# BLE112_Breakout_Board_v2_2.net
KiCad netlist of a schematic drawn in EAGLE
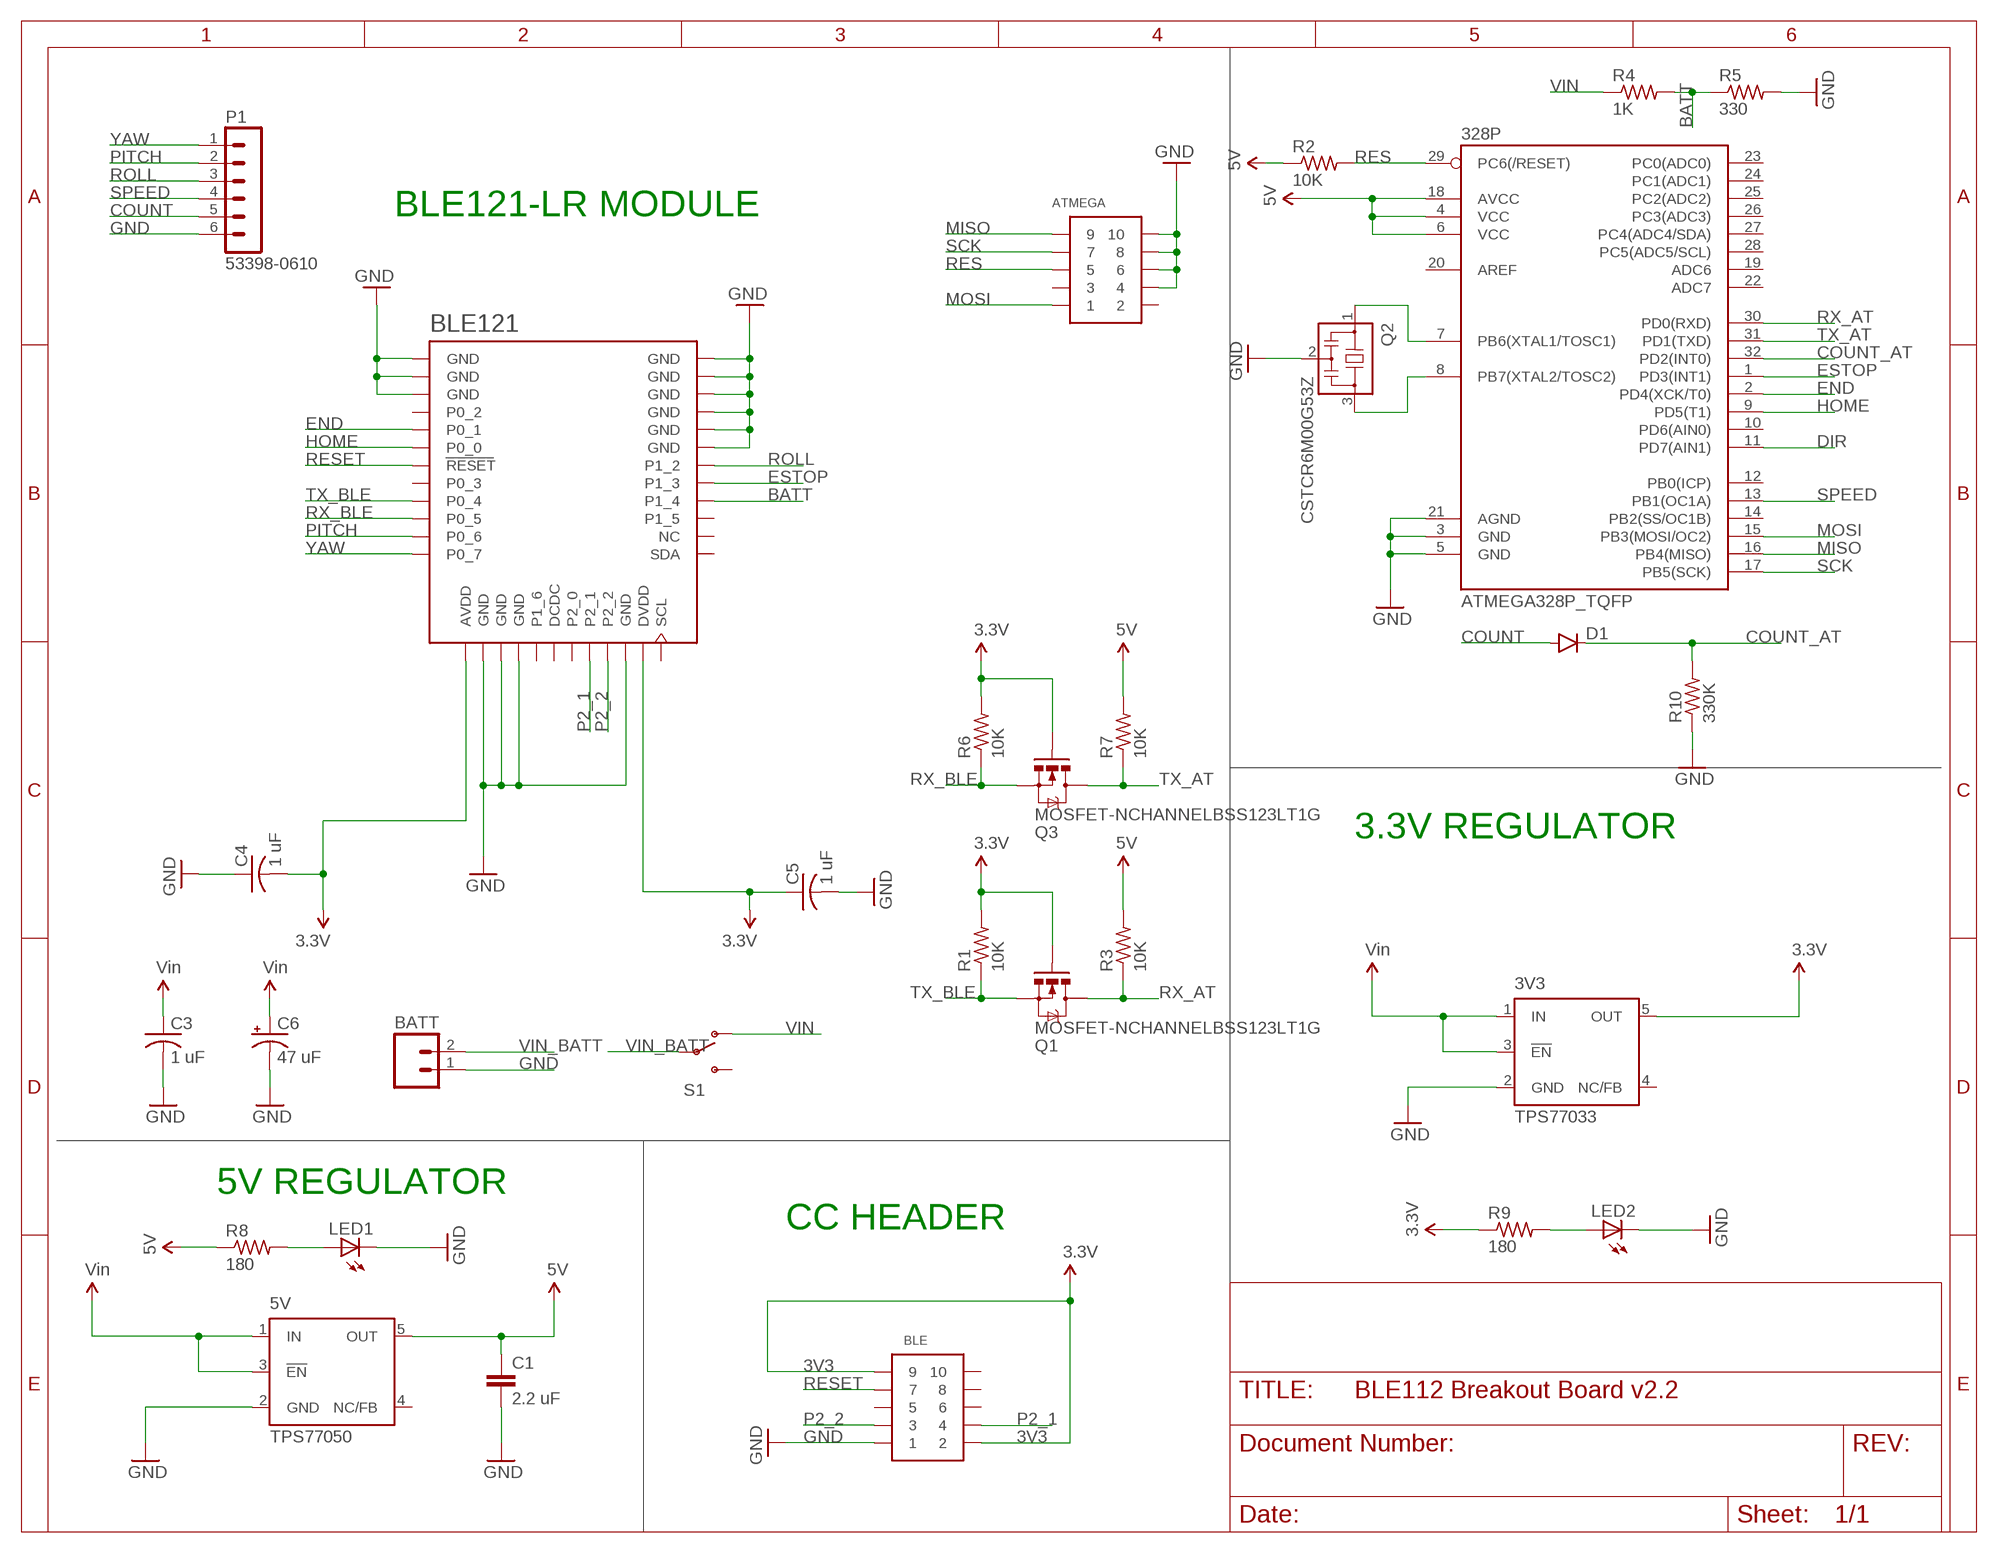
[diagram p0: schematic, sheet 1]

(export (version "E")
  (design (tool "Eeschema 10.0.6"))
  (components
    (comp (ref "3V3")
      (value "TPS77033")
      (footprint "eagle-import:SOT23-DBV")
      (fields (field (name "MF") "TEXAS INSTRUMENTS") (field (name "MPN") "TPS77033DBVT"))
      (libsource (lib "eagle-import") (part "TPS77033"))
    )
    (comp (ref "5V")
      (value "TPS77050")
      (footprint "eagle-import:SOT23-DBV")
      (fields (field (name "MF") "TEXAS INSTRUMENT CONNECTORS") (field (name "MPN") "TPS77050DBVT"))
      (libsource (lib "eagle-import") (part "TPS77050"))
    )
    (comp (ref "328P")
      (value "ATMEGA328P_TQFP")
      (footprint "eagle-import:TQFP32-08")
      (libsource (lib "eagle-import") (part "ATMEGA328P_TQFP"))
    )
    (comp (ref "ATMEGA")
      (value "CONN_5-2-FTSH-V")
      (footprint "eagle-import:FTSH-105-DV")
      (libsource (lib "eagle-import") (part "CONN_5-2-FTSH-V"))
    )
    (comp (ref "BATT")
      (value "M02JST-PTH-2")
      (footprint "eagle-import:JST-2-PTH")
      (libsource (lib "eagle-import") (part "M02JST-PTH-2"))
    )
    (comp (ref "BLE")
      (value "CONN_5-2-FTSH-V")
      (footprint "eagle-import:FTSH-105-DV")
      (libsource (lib "eagle-import") (part "CONN_5-2-FTSH-V"))
    )
    (comp (ref "BLE121")
      (value "BLE121LR-VISUAL-A")
      (footprint "eagle-import:BLE121LR-A")
      (libsource (lib "eagle-import") (part "BLE121LR-VISUAL-A"))
    )
    (comp (ref "C1")
      (value "2.2 uF")
      (footprint "eagle-import:0603-CAP")
      (libsource (lib "eagle-import") (part "CAP0603-CAP"))
    )
    (comp (ref "C3")
      (value "1 uF")
      (footprint "eagle-import:C0402")
      (libsource (lib "eagle-import") (part "C-USC0402"))
    )
    (comp (ref "C4")
      (value "1 uF")
      (footprint "eagle-import:C0402")
      (libsource (lib "eagle-import") (part "C-USC0402"))
    )
    (comp (ref "C5")
      (value "1 uF")
      (footprint "eagle-import:C0402")
      (libsource (lib "eagle-import") (part "C-USC0402"))
    )
    (comp (ref "C6")
      (value "47 uF")
      (footprint "eagle-import:PANASONIC_D")
      (libsource (lib "eagle-import") (part "CPOL-USD"))
    )
    (comp (ref "D1")
      (value "DIODESOT23")
      (footprint "eagle-import:SOT23-3")
      (libsource (lib "eagle-import") (part "DIODESOT23"))
    )
    (comp (ref "LED1")
      (value "LEDSML0603")
      (footprint "eagle-import:SML0603")
      (libsource (lib "eagle-import") (part "LEDSML0603"))
    )
    (comp (ref "LED2")
      (value "LEDSML0603")
      (footprint "eagle-import:SML0603")
      (libsource (lib "eagle-import") (part "LEDSML0603"))
    )
    (comp (ref "P1")
      (value "53398-0610")
      (footprint "eagle-import:53398-0610")
      (libsource (lib "eagle-import") (part "53398-0610"))
    )
    (comp (ref "Q1")
      (value "MOSFET-NCHANNELBSS123LT1G")
      (footprint "eagle-import:SOT23-3")
      (libsource (lib "eagle-import") (part "MOSFET-NCHANNELBSS123LT1G"))
    )
    (comp (ref "Q2")
      (value "CSTCR6M00G53Z")
      (footprint "eagle-import:CSTCR6M")
      (fields (field (name "MPN") "CSTCR6M00G53-R0"))
      (libsource (lib "eagle-import") (part "CSTCR6M00G53Z"))
    )
    (comp (ref "Q3")
      (value "MOSFET-NCHANNELBSS123LT1G")
      (footprint "eagle-import:SOT23-3")
      (libsource (lib "eagle-import") (part "MOSFET-NCHANNELBSS123LT1G"))
    )
    (comp (ref "R1")
      (value "10K")
      (footprint "eagle-import:R0402")
      (libsource (lib "eagle-import") (part "R-US_R0402"))
    )
    (comp (ref "R2")
      (value "10K")
      (footprint "eagle-import:R0402")
      (libsource (lib "eagle-import") (part "R-US_R0402"))
    )
    (comp (ref "R3")
      (value "10K")
      (footprint "eagle-import:R0402")
      (libsource (lib "eagle-import") (part "R-US_R0402"))
    )
    (comp (ref "R4")
      (value "1K")
      (footprint "eagle-import:R0402")
      (libsource (lib "eagle-import") (part "R-US_R0402"))
    )
    (comp (ref "R5")
      (value "330")
      (footprint "eagle-import:R0402")
      (libsource (lib "eagle-import") (part "R-US_R0402"))
    )
    (comp (ref "R6")
      (value "10K")
      (footprint "eagle-import:R0402")
      (libsource (lib "eagle-import") (part "R-US_R0402"))
    )
    (comp (ref "R7")
      (value "10K")
      (footprint "eagle-import:R0402")
      (libsource (lib "eagle-import") (part "R-US_R0402"))
    )
    (comp (ref "R8")
      (value "180")
      (footprint "eagle-import:R0402")
      (libsource (lib "eagle-import") (part "R-US_R0402"))
    )
    (comp (ref "R9")
      (value "180")
      (footprint "eagle-import:R0402")
      (libsource (lib "eagle-import") (part "R-US_R0402"))
    )
    (comp (ref "R10")
      (value "330K")
      (footprint "eagle-import:R0402")
      (libsource (lib "eagle-import") (part "R-US_R0402"))
    )
    (comp (ref "S1")
      (value "SWITCH-SPDTSMD")
      (footprint "eagle-import:AYZ0202")
      (libsource (lib "eagle-import") (part "SWITCH-SPDTSMD"))
    )
  )
  (nets
    (net (code "1") (name "/BATT") (class "Default")
      (node (ref "BLE121") (pin "P1_4") (pinfunction "P1_4_P1_4") (pintype "bidirectional"))
      (node (ref "R4") (pin "2") (pinfunction "2_2") (pintype "passive"))
      (node (ref "R5") (pin "1") (pinfunction "1_1") (pintype "passive"))
    )
    (net (code "2") (name "/COUNT") (class "Default")
      (node (ref "D1") (pin "1") (pinfunction "A_1") (pintype "passive"))
      (node (ref "P1") (pin "5") (pinfunction "5_5") (pintype "passive"))
    )
    (net (code "3") (name "/COUNT_AT") (class "Default")
      (node (ref "328P") (pin "32") (pinfunction "PD2(INT0)_32") (pintype "bidirectional"))
      (node (ref "D1") (pin "3") (pinfunction "C_3") (pintype "passive"))
      (node (ref "R10") (pin "2") (pinfunction "2_2") (pintype "passive"))
    )
    (net (code "4") (name "/DIR") (class "Default")
      (node (ref "328P") (pin "11") (pinfunction "PD7(AIN1)_11") (pintype "bidirectional"))
    )
    (net (code "5") (name "/END") (class "Default")
      (node (ref "328P") (pin "2") (pinfunction "PD4(XCK/T0)_2") (pintype "bidirectional"))
      (node (ref "BLE121") (pin "P0_1") (pinfunction "P0_1_P0_1") (pintype "bidirectional"))
    )
    (net (code "6") (name "/ESTOP") (class "Default")
      (node (ref "328P") (pin "1") (pinfunction "PD3(INT1)_1") (pintype "bidirectional"))
      (node (ref "BLE121") (pin "P1_3") (pinfunction "P1_3_P1_3") (pintype "bidirectional"))
    )
    (net (code "7") (name "/HOME") (class "Default")
      (node (ref "328P") (pin "9") (pinfunction "PD5(T1)_9") (pintype "bidirectional"))
      (node (ref "BLE121") (pin "P0_0") (pinfunction "P0_0_P0_0") (pintype "bidirectional"))
    )
    (net (code "8") (name "/MISO") (class "Default")
      (node (ref "328P") (pin "16") (pinfunction "PB4(MISO)_16") (pintype "bidirectional"))
      (node (ref "ATMEGA") (pin "9") (pinfunction "9_9") (pintype "bidirectional"))
    )
    (net (code "9") (name "/MOSI") (class "Default")
      (node (ref "328P") (pin "15") (pinfunction "PB3(MOSI/OC2)_15") (pintype "bidirectional"))
      (node (ref "ATMEGA") (pin "1") (pinfunction "1_1") (pintype "bidirectional"))
    )
    (net (code "10") (name "/P2_1") (class "Default")
      (node (ref "BLE") (pin "4") (pinfunction "4_4") (pintype "bidirectional"))
      (node (ref "BLE121") (pin "P2_1") (pinfunction "P2_1_P2_1") (pintype "bidirectional"))
    )
    (net (code "11") (name "/P2_2") (class "Default")
      (node (ref "BLE") (pin "3") (pinfunction "3_3") (pintype "bidirectional"))
      (node (ref "BLE121") (pin "P2_2") (pinfunction "P2_2_P2_2") (pintype "bidirectional"))
    )
    (net (code "12") (name "/PITCH") (class "Default")
      (node (ref "BLE121") (pin "P0_6") (pinfunction "P0_6_P0_6") (pintype "bidirectional"))
      (node (ref "P1") (pin "2") (pinfunction "2_2") (pintype "passive"))
    )
    (net (code "13") (name "/RES") (class "Default")
      (node (ref "328P") (pin "29") (pinfunction "PC6(/RESET)_29") (pintype "bidirectional"))
      (node (ref "ATMEGA") (pin "5") (pinfunction "5_5") (pintype "bidirectional"))
      (node (ref "R2") (pin "2") (pinfunction "2_2") (pintype "passive"))
    )
    (net (code "14") (name "/RESET") (class "Default")
      (node (ref "BLE") (pin "7") (pinfunction "7_7") (pintype "bidirectional"))
      (node (ref "BLE121") (pin "RESET") (pinfunction "RESET_RESET") (pintype "input"))
    )
    (net (code "15") (name "/ROLL") (class "Default")
      (node (ref "BLE121") (pin "P1_2") (pinfunction "P1_2_P1_2") (pintype "bidirectional"))
      (node (ref "P1") (pin "3") (pinfunction "3_3") (pintype "passive"))
    )
    (net (code "16") (name "/RX_AT") (class "Default")
      (node (ref "328P") (pin "30") (pinfunction "PD0(RXD)_30") (pintype "bidirectional"))
      (node (ref "Q1") (pin "3") (pinfunction "D_3") (pintype "passive"))
      (node (ref "R3") (pin "1") (pinfunction "1_1") (pintype "passive"))
    )
    (net (code "17") (name "/RX_BLE") (class "Default")
      (node (ref "BLE121") (pin "P0_5") (pinfunction "P0_5_P0_5") (pintype "bidirectional"))
      (node (ref "Q3") (pin "2") (pinfunction "S_2") (pintype "passive"))
      (node (ref "R6") (pin "1") (pinfunction "1_1") (pintype "passive"))
    )
    (net (code "18") (name "/SCK") (class "Default")
      (node (ref "328P") (pin "17") (pinfunction "PB5(SCK)_17") (pintype "bidirectional"))
      (node (ref "ATMEGA") (pin "7") (pinfunction "7_7") (pintype "bidirectional"))
    )
    (net (code "19") (name "/SPEED") (class "Default")
      (node (ref "328P") (pin "13") (pinfunction "PB1(OC1A)_13") (pintype "bidirectional"))
      (node (ref "P1") (pin "4") (pinfunction "4_4") (pintype "passive"))
    )
    (net (code "20") (name "/TX_AT") (class "Default")
      (node (ref "328P") (pin "31") (pinfunction "PD1(TXD)_31") (pintype "bidirectional"))
      (node (ref "Q3") (pin "3") (pinfunction "D_3") (pintype "passive"))
      (node (ref "R7") (pin "1") (pinfunction "1_1") (pintype "passive"))
    )
    (net (code "21") (name "/TX_BLE") (class "Default")
      (node (ref "BLE121") (pin "P0_4") (pinfunction "P0_4_P0_4") (pintype "bidirectional"))
      (node (ref "Q1") (pin "2") (pinfunction "S_2") (pintype "passive"))
      (node (ref "R1") (pin "1") (pinfunction "1_1") (pintype "passive"))
    )
    (net (code "22") (name "/VIN_BATT") (class "Default")
      (node (ref "BATT") (pin "2") (pinfunction "2_2") (pintype "passive"))
      (node (ref "S1") (pin "2") (pinfunction "P_2") (pintype "passive"))
    )
    (net (code "23") (name "/YAW") (class "Default")
      (node (ref "BLE121") (pin "P0_7") (pinfunction "P0_7_P0_7") (pintype "bidirectional"))
      (node (ref "P1") (pin "1") (pinfunction "1_1") (pintype "passive"))
    )
    (net (code "24") (name "3.3V") (class "Default")
      (node (ref "3V3") (pin "5") (pinfunction "OUT_5") (pintype "passive"))
      (node (ref "BLE") (pin "2") (pinfunction "2_2") (pintype "bidirectional"))
      (node (ref "BLE") (pin "9") (pinfunction "9_9") (pintype "bidirectional"))
      (node (ref "BLE121") (pin "AVDD") (pinfunction "AVDD_AVDD") (pintype "power_in"))
      (node (ref "BLE121") (pin "DVDD") (pinfunction "DVDD_DVDD") (pintype "power_in"))
      (node (ref "C4") (pin "2") (pinfunction "2_2") (pintype "passive"))
      (node (ref "C5") (pin "1") (pinfunction "1_1") (pintype "passive"))
      (node (ref "Q1") (pin "1") (pinfunction "G_1") (pintype "passive"))
      (node (ref "Q3") (pin "1") (pinfunction "G_1") (pintype "passive"))
      (node (ref "R1") (pin "2") (pinfunction "2_2") (pintype "passive"))
      (node (ref "R6") (pin "2") (pinfunction "2_2") (pintype "passive"))
      (node (ref "R9") (pin "1") (pinfunction "1_1") (pintype "passive"))
    )
    (net (code "25") (name "5V") (class "Default")
      (node (ref "328P") (pin "18") (pinfunction "AVCC_18") (pintype "bidirectional"))
      (node (ref "328P") (pin "4") (pinfunction "VCC_4") (pintype "bidirectional"))
      (node (ref "328P") (pin "6") (pinfunction "VCC_6") (pintype "bidirectional"))
      (node (ref "5V") (pin "5") (pinfunction "OUT_5") (pintype "passive"))
      (node (ref "C1") (pin "1") (pinfunction "1_1") (pintype "passive"))
      (node (ref "R2") (pin "1") (pinfunction "1_1") (pintype "passive"))
      (node (ref "R3") (pin "2") (pinfunction "2_2") (pintype "passive"))
      (node (ref "R7") (pin "2") (pinfunction "2_2") (pintype "passive"))
      (node (ref "R8") (pin "1") (pinfunction "1_1") (pintype "passive"))
    )
    (net (code "26") (name "GND") (class "Default")
      (node (ref "328P") (pin "21") (pinfunction "AGND_21") (pintype "bidirectional"))
      (node (ref "328P") (pin "3") (pinfunction "GND_3") (pintype "bidirectional"))
      (node (ref "328P") (pin "5") (pinfunction "GND_5") (pintype "bidirectional"))
      (node (ref "3V3") (pin "2") (pinfunction "GND_2") (pintype "power_in"))
      (node (ref "5V") (pin "2") (pinfunction "GND_2") (pintype "power_in"))
      (node (ref "ATMEGA") (pin "10") (pinfunction "10_10") (pintype "bidirectional"))
      (node (ref "ATMEGA") (pin "4") (pinfunction "4_4") (pintype "bidirectional"))
      (node (ref "ATMEGA") (pin "6") (pinfunction "6_6") (pintype "bidirectional"))
      (node (ref "ATMEGA") (pin "8") (pinfunction "8_8") (pintype "bidirectional"))
      (node (ref "BATT") (pin "1") (pinfunction "1_1") (pintype "passive"))
      (node (ref "BLE") (pin "1") (pinfunction "1_1") (pintype "bidirectional"))
      (node (ref "BLE121") (pin "GND") (pinfunction "GND_GND") (pintype "power_in"))
      (node (ref "BLE121") (pin "GND@10") (pinfunction "GND_GND@10") (pintype "power_in"))
      (node (ref "BLE121") (pin "GND@11") (pinfunction "GND_GND@11") (pintype "power_in"))
      (node (ref "BLE121") (pin "GND@12") (pinfunction "GND_GND@12") (pintype "power_in"))
      (node (ref "BLE121") (pin "GND@13") (pinfunction "GND_GND@13") (pintype "power_in"))
      (node (ref "BLE121") (pin "GND@2") (pinfunction "GND_GND@2") (pintype "power_in"))
      (node (ref "BLE121") (pin "GND@3") (pinfunction "GND_GND@3") (pintype "power_in"))
      (node (ref "BLE121") (pin "GND@4") (pinfunction "GND_GND@4") (pintype "power_in"))
      (node (ref "BLE121") (pin "GND@5") (pinfunction "GND_GND@5") (pintype "power_in"))
      (node (ref "BLE121") (pin "GND@6") (pinfunction "GND_GND@6") (pintype "power_in"))
      (node (ref "BLE121") (pin "GND@7") (pinfunction "GND_GND@7") (pintype "power_in"))
      (node (ref "BLE121") (pin "GND@8") (pinfunction "GND_GND@8") (pintype "power_in"))
      (node (ref "BLE121") (pin "GND@9") (pinfunction "GND_GND@9") (pintype "power_in"))
      (node (ref "C1") (pin "2") (pinfunction "2_2") (pintype "passive"))
      (node (ref "C3") (pin "2") (pinfunction "2_2") (pintype "passive"))
      (node (ref "C4") (pin "1") (pinfunction "1_1") (pintype "passive"))
      (node (ref "C5") (pin "2") (pinfunction "2_2") (pintype "passive"))
      (node (ref "C6") (pin "-") (pinfunction "-_-") (pintype "passive"))
      (node (ref "LED1") (pin "C") (pinfunction "C_C") (pintype "passive"))
      (node (ref "LED2") (pin "C") (pinfunction "C_C") (pintype "passive"))
      (node (ref "P1") (pin "6") (pinfunction "6_6") (pintype "passive"))
      (node (ref "Q2") (pin "2") (pinfunction "2_2") (pintype "passive"))
      (node (ref "R10") (pin "1") (pinfunction "1_1") (pintype "passive"))
      (node (ref "R5") (pin "2") (pinfunction "2_2") (pintype "passive"))
    )
    (net (code "27") (name "Net-(328P-PB6(XTAL1{slash}TOSC1))") (class "Default")
      (node (ref "328P") (pin "7") (pinfunction "PB6(XTAL1/TOSC1)_7") (pintype "bidirectional"))
      (node (ref "Q2") (pin "1") (pinfunction "1_1") (pintype "passive"))
    )
    (net (code "28") (name "Net-(328P-PB7(XTAL2{slash}TOSC2))") (class "Default")
      (node (ref "328P") (pin "8") (pinfunction "PB7(XTAL2/TOSC2)_8") (pintype "bidirectional"))
      (node (ref "Q2") (pin "3") (pinfunction "3_3") (pintype "passive"))
    )
    (net (code "29") (name "Net-(LED1-PadA)") (class "Default")
      (node (ref "LED1") (pin "A") (pinfunction "A_A") (pintype "passive"))
      (node (ref "R8") (pin "2") (pinfunction "2_2") (pintype "passive"))
    )
    (net (code "30") (name "Net-(LED2-PadA)") (class "Default")
      (node (ref "LED2") (pin "A") (pinfunction "A_A") (pintype "passive"))
      (node (ref "R9") (pin "2") (pinfunction "2_2") (pintype "passive"))
    )
    (net (code "31") (name "Vin") (class "Default")
      (node (ref "3V3") (pin "1") (pinfunction "IN_1") (pintype "input"))
      (node (ref "3V3") (pin "3") (pinfunction "~{EN}_3") (pintype "input"))
      (node (ref "5V") (pin "1") (pinfunction "IN_1") (pintype "input"))
      (node (ref "5V") (pin "3") (pinfunction "~{EN}_3") (pintype "input"))
      (node (ref "C3") (pin "1") (pinfunction "1_1") (pintype "passive"))
      (node (ref "C6") (pin "+") (pinfunction "+_+") (pintype "passive"))
      (node (ref "R4") (pin "1") (pinfunction "1_1") (pintype "passive"))
      (node (ref "S1") (pin "1") (pinfunction "O_1") (pintype "passive"))
    )
    (net (code "32") (name "unconnected-(3V3-NC{slash}FB-Pad4)") (class "Default")
      (node (ref "3V3") (pin "4") (pinfunction "NC/FB_4") (pintype "passive"))
    )
    (net (code "33") (name "unconnected-(5V-NC{slash}FB-Pad4)") (class "Default")
      (node (ref "5V") (pin "4") (pinfunction "NC/FB_4") (pintype "passive"))
    )
    (net (code "34") (name "unconnected-(328P-ADC6-Pad19)") (class "Default")
      (node (ref "328P") (pin "19") (pinfunction "ADC6_19") (pintype "bidirectional"))
    )
    (net (code "35") (name "unconnected-(328P-ADC7-Pad22)") (class "Default")
      (node (ref "328P") (pin "22") (pinfunction "ADC7_22") (pintype "bidirectional"))
    )
    (net (code "36") (name "unconnected-(328P-AREF-Pad20)") (class "Default")
      (node (ref "328P") (pin "20") (pinfunction "AREF_20") (pintype "bidirectional"))
    )
    (net (code "37") (name "unconnected-(328P-PB0(ICP)-Pad12)") (class "Default")
      (node (ref "328P") (pin "12") (pinfunction "PB0(ICP)_12") (pintype "bidirectional"))
    )
    (net (code "38") (name "unconnected-(328P-PB2(SS{slash}OC1B)-Pad14)") (class "Default")
      (node (ref "328P") (pin "14") (pinfunction "PB2(SS/OC1B)_14") (pintype "bidirectional"))
    )
    (net (code "39") (name "unconnected-(328P-PC0(ADC0)-Pad23)") (class "Default")
      (node (ref "328P") (pin "23") (pinfunction "PC0(ADC0)_23") (pintype "bidirectional"))
    )
    (net (code "40") (name "unconnected-(328P-PC1(ADC1)-Pad24)") (class "Default")
      (node (ref "328P") (pin "24") (pinfunction "PC1(ADC1)_24") (pintype "bidirectional"))
    )
    (net (code "41") (name "unconnected-(328P-PC2(ADC2)-Pad25)") (class "Default")
      (node (ref "328P") (pin "25") (pinfunction "PC2(ADC2)_25") (pintype "bidirectional"))
    )
    (net (code "42") (name "unconnected-(328P-PC3(ADC3)-Pad26)") (class "Default")
      (node (ref "328P") (pin "26") (pinfunction "PC3(ADC3)_26") (pintype "bidirectional"))
    )
    (net (code "43") (name "unconnected-(328P-PC4(ADC4{slash}SDA)-Pad27)") (class "Default")
      (node (ref "328P") (pin "27") (pinfunction "PC4(ADC4/SDA)_27") (pintype "bidirectional"))
    )
    (net (code "44") (name "unconnected-(328P-PC5(ADC5{slash}SCL)-Pad28)") (class "Default")
      (node (ref "328P") (pin "28") (pinfunction "PC5(ADC5/SCL)_28") (pintype "bidirectional"))
    )
    (net (code "45") (name "unconnected-(328P-PD6(AIN0)-Pad10)") (class "Default")
      (node (ref "328P") (pin "10") (pinfunction "PD6(AIN0)_10") (pintype "bidirectional"))
    )
    (net (code "46") (name "unconnected-(ATMEGA-Pad2)") (class "Default")
      (node (ref "ATMEGA") (pin "2") (pinfunction "2_2") (pintype "bidirectional"))
    )
    (net (code "47") (name "unconnected-(ATMEGA-Pad3)") (class "Default")
      (node (ref "ATMEGA") (pin "3") (pinfunction "3_3") (pintype "bidirectional"))
    )
    (net (code "48") (name "unconnected-(BLE-Pad5)") (class "Default")
      (node (ref "BLE") (pin "5") (pinfunction "5_5") (pintype "bidirectional"))
    )
    (net (code "49") (name "unconnected-(BLE-Pad6)") (class "Default")
      (node (ref "BLE") (pin "6") (pinfunction "6_6") (pintype "bidirectional"))
    )
    (net (code "50") (name "unconnected-(BLE-Pad8)") (class "Default")
      (node (ref "BLE") (pin "8") (pinfunction "8_8") (pintype "bidirectional"))
    )
    (net (code "51") (name "unconnected-(BLE-Pad10)") (class "Default")
      (node (ref "BLE") (pin "10") (pinfunction "10_10") (pintype "bidirectional"))
    )
    (net (code "52") (name "unconnected-(BLE121-PadDCDC)") (class "Default")
      (node (ref "BLE121") (pin "DCDC") (pinfunction "DCDC_DCDC") (pintype "bidirectional"))
    )
    (net (code "53") (name "unconnected-(BLE121-PadNC)") (class "Default")
      (node (ref "BLE121") (pin "NC") (pinfunction "NC_NC") (pintype "no_connect"))
    )
    (net (code "54") (name "unconnected-(BLE121-PadP0_2)") (class "Default")
      (node (ref "BLE121") (pin "P0_2") (pinfunction "P0_2_P0_2") (pintype "bidirectional"))
    )
    (net (code "55") (name "unconnected-(BLE121-PadP0_3)") (class "Default")
      (node (ref "BLE121") (pin "P0_3") (pinfunction "P0_3_P0_3") (pintype "bidirectional"))
    )
    (net (code "56") (name "unconnected-(BLE121-PadP1_5)") (class "Default")
      (node (ref "BLE121") (pin "P1_5") (pinfunction "P1_5_P1_5") (pintype "bidirectional"))
    )
    (net (code "57") (name "unconnected-(BLE121-PadP1_6)") (class "Default")
      (node (ref "BLE121") (pin "P1_6") (pinfunction "P1_6_P1_6") (pintype "bidirectional"))
    )
    (net (code "58") (name "unconnected-(BLE121-PadP2_0)") (class "Default")
      (node (ref "BLE121") (pin "P2_0") (pinfunction "P2_0_P2_0") (pintype "bidirectional"))
    )
    (net (code "59") (name "unconnected-(BLE121-PadSCL)") (class "Default")
      (node (ref "BLE121") (pin "SCL") (pinfunction "SCL_SCL") (pintype "bidirectional"))
    )
    (net (code "60") (name "unconnected-(BLE121-PadSDA)") (class "Default")
      (node (ref "BLE121") (pin "SDA") (pinfunction "SDA_SDA") (pintype "bidirectional"))
    )
    (net (code "61") (name "unconnected-(S1-S-Pad3)") (class "Default")
      (node (ref "S1") (pin "3") (pinfunction "S_3") (pintype "passive"))
    )
  )
)
